# can_12V_step_Ivan.net
KiCad netlist of a schematic drawn in Altium Designer
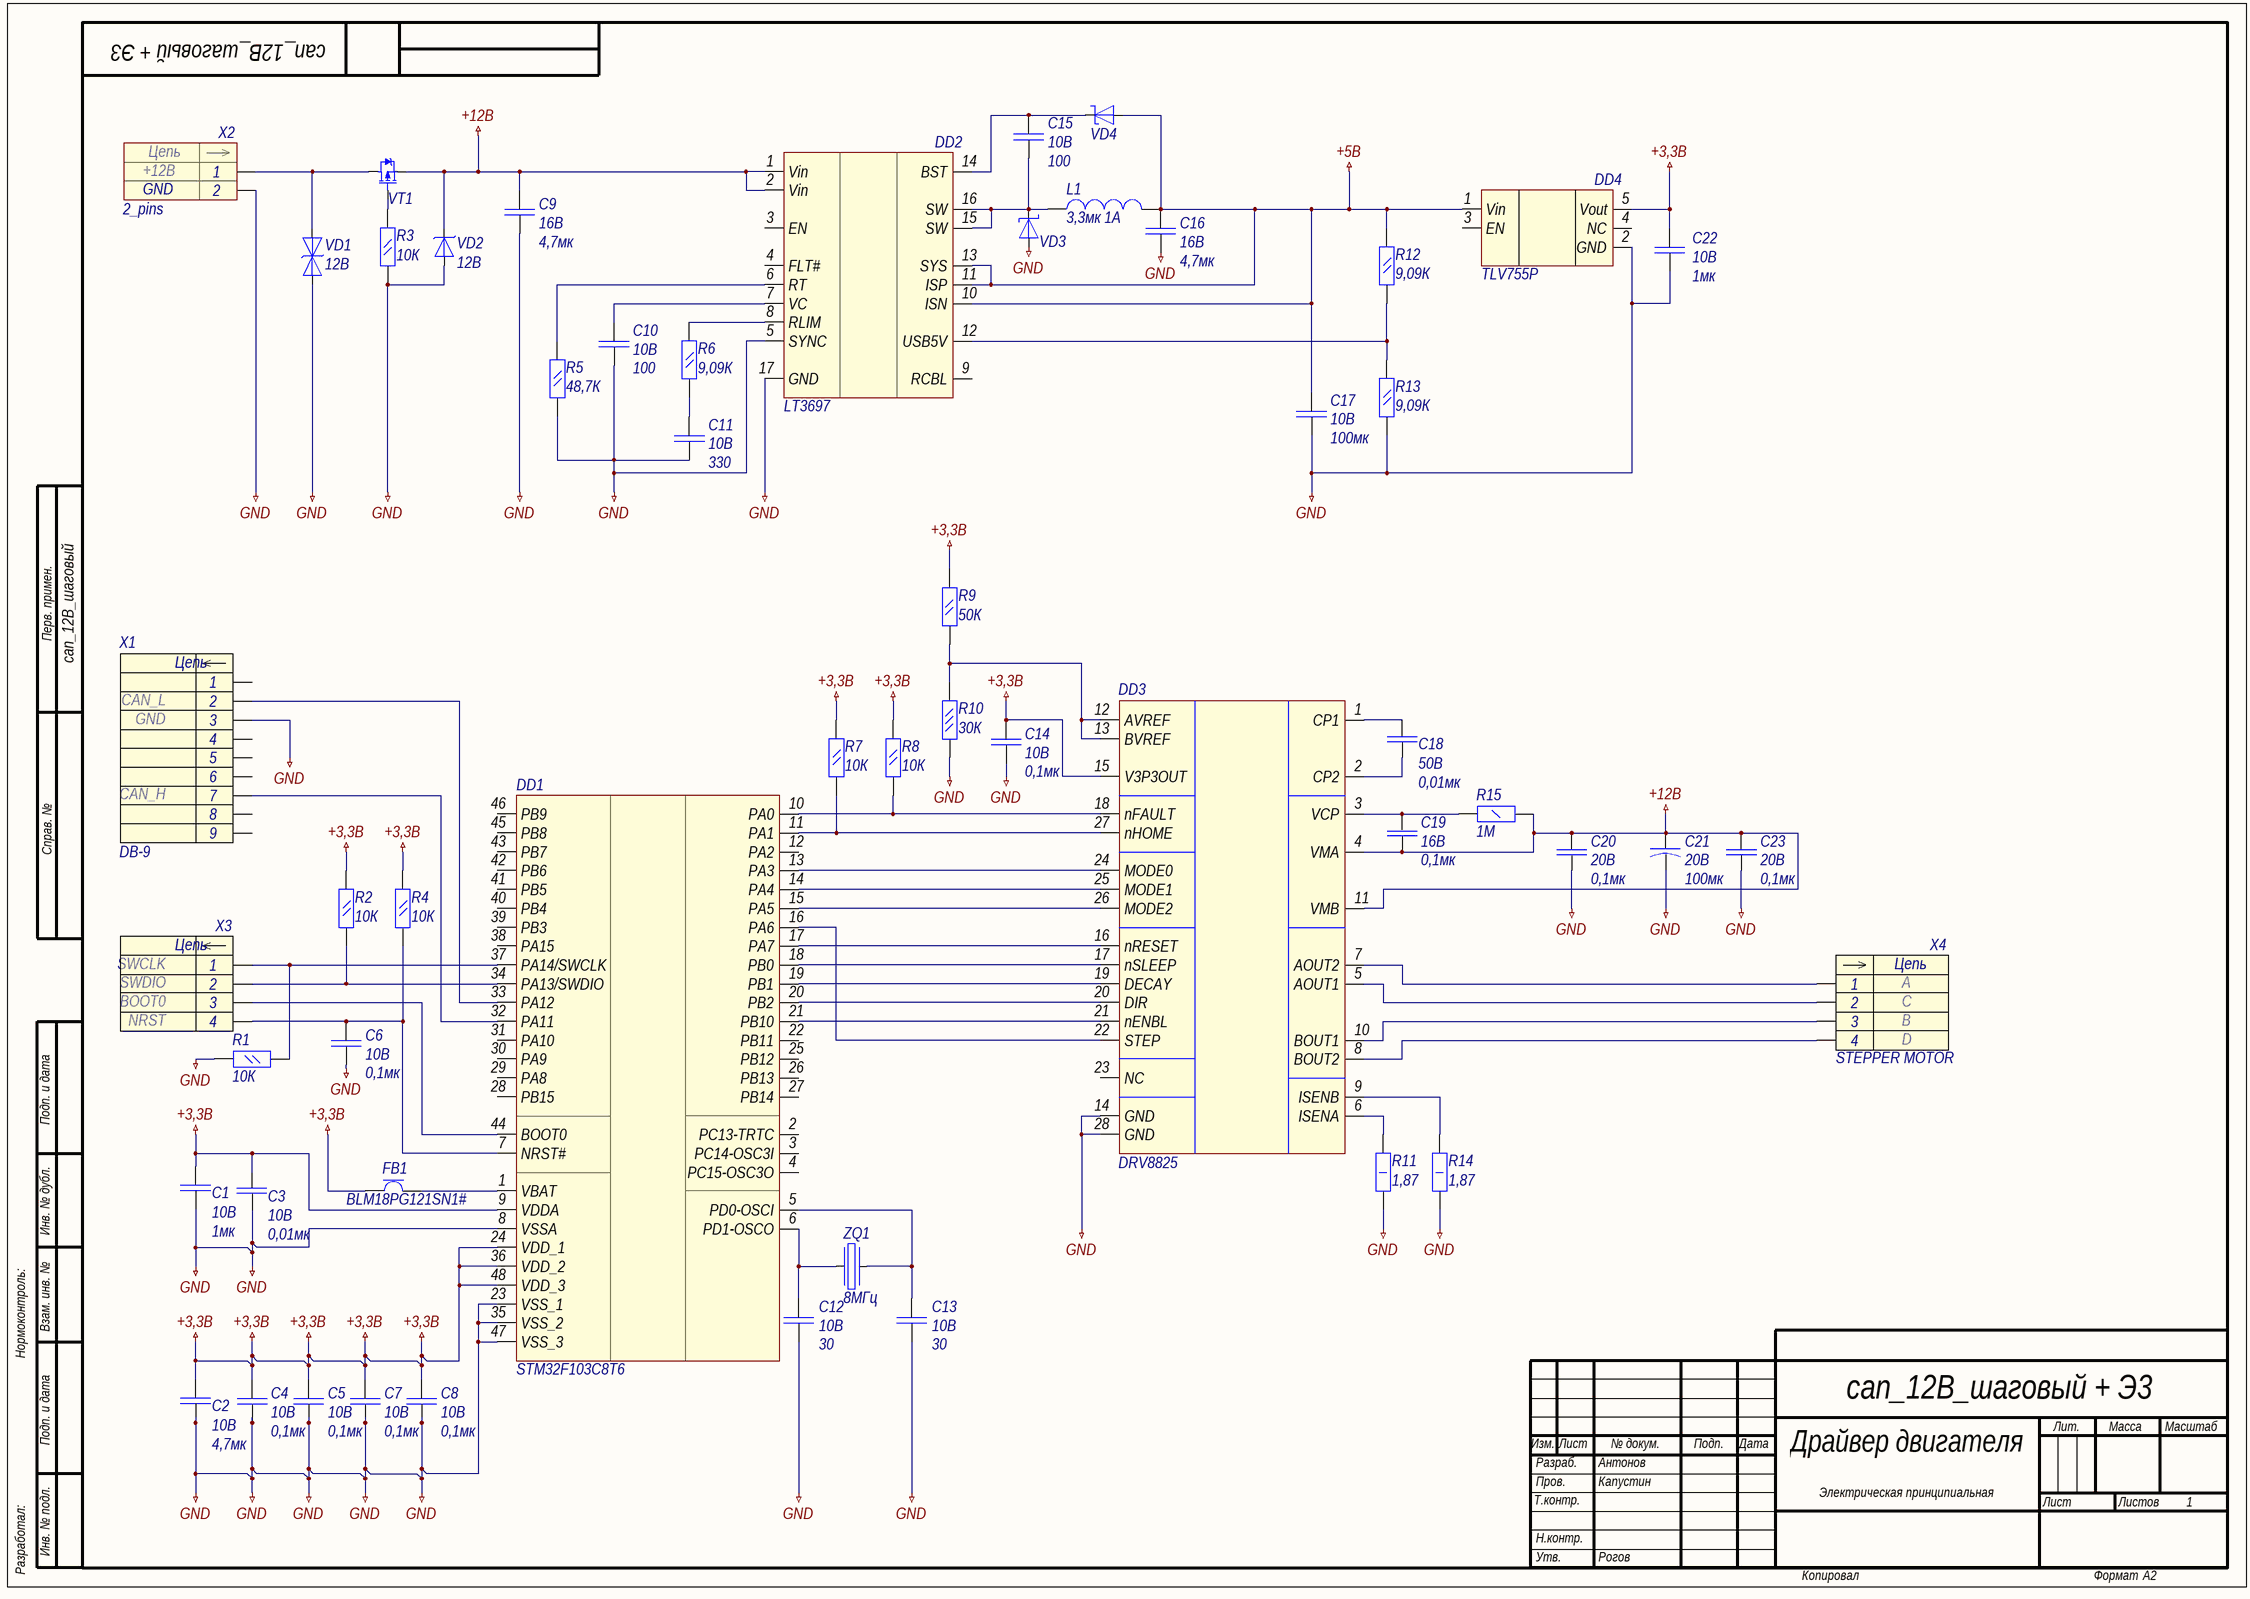
[diagram p0: can_12V_step_Ivan.SchDoc]

(export (version "E")
  (design (tool "Eeschema 10.0.6"))
  (components
    (comp (ref "C1")
      (value "Capacitor")
      (footprint "CH0201C")
      (fields (field (name "VOLTAGE") "10В") (field (name "CAPACITANCE") "1мк"))
      (libsource (lib "") (part "Capacitor_1"))
    )
    (comp (ref "C2")
      (value "Capacitor")
      (footprint "CH0402C")
      (fields (field (name "VOLTAGE") "10В") (field (name "CAPACITANCE") "4,7мк"))
      (libsource (lib "") (part "Capacitor_1"))
    )
    (comp (ref "C3")
      (value "Capacitor")
      (footprint "CH0402C")
      (fields (field (name "VOLTAGE") "10В") (field (name "CAPACITANCE") "0,01мк"))
      (libsource (lib "GOST_Capacitors") (part "Capacitor"))
    )
    (comp (ref "C4")
      (value "Capacitor")
      (footprint "CH0402C")
      (fields (field (name "VOLTAGE") "10В") (field (name "CAPACITANCE") "0,1мк"))
      (libsource (lib "") (part "Capacitor_1"))
    )
    (comp (ref "C5")
      (value "Capacitor")
      (footprint "CH0402C")
      (fields (field (name "VOLTAGE") "10В") (field (name "CAPACITANCE") "0,1мк"))
      (libsource (lib "") (part "Capacitor_1"))
    )
    (comp (ref "C6")
      (value "Capacitor")
      (footprint "CH0402C")
      (fields (field (name "VOLTAGE") "10В") (field (name "CAPACITANCE") "0,1мк"))
      (libsource (lib "") (part "Capacitor_1"))
    )
    (comp (ref "C7")
      (value "Capacitor")
      (footprint "CH0402C")
      (fields (field (name "VOLTAGE") "10В") (field (name "CAPACITANCE") "0,1мк"))
      (libsource (lib "") (part "Capacitor_1"))
    )
    (comp (ref "C8")
      (value "Capacitor")
      (footprint "CH0402C")
      (fields (field (name "VOLTAGE") "10В") (field (name "CAPACITANCE") "0,1мк"))
      (libsource (lib "") (part "Capacitor_1"))
    )
    (comp (ref "C9")
      (value "Capacitor")
      (footprint "CH0603C")
      (fields (field (name "VOLTAGE") "16В") (field (name "CAPACITANCE") "4,7мк"))
      (libsource (lib "") (part "Capacitor_1"))
    )
    (comp (ref "C10")
      (value "Capacitor")
      (footprint "CH0201C")
      (fields (field (name "VOLTAGE") "10В") (field (name "CAPACITANCE") "100"))
      (libsource (lib "") (part "Capacitor_1"))
    )
    (comp (ref "C11")
      (value "Capacitor")
      (footprint "CH0402C")
      (fields (field (name "VOLTAGE") "10В") (field (name "CAPACITANCE") "330"))
      (libsource (lib "") (part "Capacitor_1"))
    )
    (comp (ref "C12")
      (value "Capacitor")
      (footprint "CH0201C")
      (fields (field (name "VOLTAGE") "10В") (field (name "CAPACITANCE") "30"))
      (libsource (lib "") (part "Capacitor_1"))
    )
    (comp (ref "C13")
      (value "Capacitor")
      (footprint "CH0201C")
      (fields (field (name "VOLTAGE") "10В") (field (name "CAPACITANCE") "30"))
      (libsource (lib "") (part "Capacitor_1"))
    )
    (comp (ref "C14")
      (value "Capacitor")
      (footprint "CH0402C")
      (fields (field (name "VOLTAGE") "10В") (field (name "CAPACITANCE") "0,1мк"))
      (libsource (lib "") (part "Capacitor_1"))
    )
    (comp (ref "C15")
      (value "Capacitor")
      (footprint "CH0201C")
      (fields (field (name "VOLTAGE") "10В") (field (name "CAPACITANCE") "100"))
      (libsource (lib "") (part "Capacitor_1"))
    )
    (comp (ref "C16")
      (value "Capacitor")
      (footprint "CH0603C")
      (fields (field (name "VOLTAGE") "16В") (field (name "CAPACITANCE") "4,7мк"))
      (libsource (lib "") (part "Capacitor_1"))
    )
    (comp (ref "C17")
      (value "Capacitor")
      (footprint "CH1206C")
      (fields (field (name "VOLTAGE") "10В") (field (name "CAPACITANCE") "100мк"))
      (libsource (lib "") (part "Capacitor_1"))
    )
    (comp (ref "C18")
      (value "Capacitor")
      (footprint "CH0402C")
      (fields (field (name "VOLTAGE") "50В") (field (name "CAPACITANCE") "0,01мк"))
      (libsource (lib "GOST_Capacitors") (part "Capacitor"))
    )
    (comp (ref "C19")
      (value "Capacitor")
      (footprint "CH0402C")
      (fields (field (name "VOLTAGE") "16В") (field (name "CAPACITANCE") "0,1мк"))
      (libsource (lib "GOST_Capacitors") (part "Capacitor"))
    )
    (comp (ref "C20")
      (value "Capacitor")
      (footprint "CH0805C")
      (fields (field (name "VOLTAGE") "20В") (field (name "CAPACITANCE") "0,1мк"))
      (libsource (lib "GOST_Capacitors") (part "Capacitor"))
    )
    (comp (ref "C21")
      (value "Capacitor_Passing")
      (footprint "RB5-10.5")
      (fields (field (name "VOLTAGE") "20В") (field (name "CAPACITANCE") "100мк"))
      (libsource (lib "GOST_Capacitors") (part "Capacitor_Passing"))
    )
    (comp (ref "C22")
      (value "Capacitor")
      (footprint "CH0201C")
      (fields (field (name "VOLTAGE") "10В") (field (name "CAPACITANCE") "1мк"))
      (libsource (lib "") (part "Capacitor_1"))
    )
    (comp (ref "C23")
      (value "Capacitor")
      (footprint "CH0805C")
      (fields (field (name "VOLTAGE") "20В") (field (name "CAPACITANCE") "0,1мк"))
      (libsource (lib "GOST_Capacitors") (part "Capacitor"))
    )
    (comp (ref "DD1")
      (value "STM32F103C8T6")
      (footprint "STM32F103 48pins")
      (libsource (lib "GOST_lib_devices") (part "STM32"))
    )
    (comp (ref "DD2")
      (value "LT3697")
      (footprint "LT3697")
      (description "6~18 to 5")
      (libsource (lib "GOST_lib_devices") (part "LT3697"))
    )
    (comp (ref "DD3")
      (value "DRV8825")
      (footprint "DRV8825")
      (libsource (lib "GOST_lib_devices") (part "DRV8825"))
    )
    (comp (ref "DD4")
      (value "TLV755P")
      (footprint "SOT23-5")
      (libsource (lib "GOST_lib_devices") (part "LDO +3.3V"))
    )
    (comp (ref "FB1")
      (value "Ferrite bead")
      (footprint "CH0603L")
      (fields (field (name "MODEL") "BLM18PG121SN1#"))
      (libsource (lib "GOST_Inductors") (part "Ferrite bead"))
    )
    (comp (ref "L1")
      (value "*")
      (footprint "CH0805L")
      (fields (field (name "MAX CURRENT") "1А") (field (name "INDUCTANCE") "3,3мк"))
      (libsource (lib "GOST_Inductors") (part "Inductor"))
    )
    (comp (ref "R1")
      (value "Res_0.125")
      (footprint "CH0805R")
      (fields (field (name "IMPEDANCE") "10К"))
      (libsource (lib "GOST_Resistors") (part "Res_0.125"))
    )
    (comp (ref "R2")
      (value "Res_0.125")
      (footprint "CH0805R")
      (fields (field (name "IMPEDANCE") "10К"))
      (libsource (lib "GOST_Resistors") (part "Res_0.125"))
    )
    (comp (ref "R3")
      (value "Res_0.125")
      (footprint "CH0402R")
      (fields (field (name "IMPEDANCE") "10К"))
      (libsource (lib "GOST_Resistors") (part "Res_0.125"))
    )
    (comp (ref "R4")
      (value "Res_0.125")
      (footprint "CH0805R")
      (fields (field (name "IMPEDANCE") "10К"))
      (libsource (lib "GOST_Resistors") (part "Res_0.125"))
    )
    (comp (ref "R5")
      (value "Res_0.125")
      (footprint "CH0805R")
      (fields (field (name "IMPEDANCE") "48,7К"))
      (libsource (lib "GOST_Resistors") (part "Res_0.125"))
    )
    (comp (ref "R6")
      (value "Res_0.125")
      (footprint "CH0805R")
      (fields (field (name "IMPEDANCE") "9,09К"))
      (libsource (lib "GOST_Resistors") (part "Res_0.125"))
    )
    (comp (ref "R7")
      (value "Res_0.125")
      (footprint "CH0805R")
      (fields (field (name "IMPEDANCE") "10К"))
      (libsource (lib "GOST_Resistors") (part "Res_0.125"))
    )
    (comp (ref "R8")
      (value "Res_0.125")
      (footprint "CH0805R")
      (fields (field (name "IMPEDANCE") "10К"))
      (libsource (lib "GOST_Resistors") (part "Res_0.125"))
    )
    (comp (ref "R9")
      (value "Res_0.125")
      (footprint "CH0603R")
      (fields (field (name "POWER") "100мВ") (field (name "IMPEDANCE") "50К"))
      (libsource (lib "") (part "Res_0.125_1"))
    )
    (comp (ref "R10")
      (value "Res_0.05")
      (footprint "CH0201R")
      (fields (field (name "POWER") "0,05В") (field (name "IMPEDANCE") "30К"))
      (libsource (lib "GOST_Resistors") (part "Res_0.05"))
    )
    (comp (ref "R11")
      (value "Res_1")
      (footprint "CH0603R")
      (fields (field (name "POWER") "1Вт") (field (name "IMPEDANCE") "1,87"))
      (libsource (lib "GOST_Resistors") (part "Res_1"))
    )
    (comp (ref "R12")
      (value "Res_0.125")
      (footprint "CH0805R")
      (fields (field (name "IMPEDANCE") "9,09К"))
      (libsource (lib "GOST_Resistors") (part "Res_0.125"))
    )
    (comp (ref "R13")
      (value "Res_0.125")
      (footprint "CH0805R")
      (fields (field (name "IMPEDANCE") "9,09К"))
      (libsource (lib "GOST_Resistors") (part "Res_0.125"))
    )
    (comp (ref "R14")
      (value "Res_1")
      (footprint "CH0603R")
      (fields (field (name "POWER") "1Вт") (field (name "IMPEDANCE") "1,87"))
      (libsource (lib "GOST_Resistors") (part "Res_1"))
    )
    (comp (ref "R15")
      (value "Res_0.5")
      (footprint "CH0805R")
      (fields (field (name "IMPEDANCE") "1М"))
      (libsource (lib "GOST_Resistors") (part "Res_0.5"))
    )
    (comp (ref "VD1")
      (value "TVS-diod_simmetrical")
      (footprint "CH0201L")
      (fields (field (name "MANUFACTURER") "Littelfuse") (field (name "CLAMPING VOLTAGE") "12В"))
      (libsource (lib "GOST_Diodes") (part "TVS-diod_simmetrical"))
    )
    (comp (ref "VD2")
      (value "TVS-diod_directed")
      (footprint "DO214AA")
      (fields (field (name "MANUFACTURER") "Bourns") (field (name "CLAMPING_VOLTAGE") "12В"))
      (libsource (lib "GOST_Diodes") (part "TVS-diod_directed"))
    )
    (comp (ref "VD3")
      (value "Diod Schottky")
      (footprint "DO214AA")
      (fields (field (name "MANUFACTURER") "Rectron"))
      (libsource (lib "GOST_Diodes") (part "Diod Schottky"))
    )
    (comp (ref "VD4")
      (value "Diod Schottky")
      (footprint "SOT23_132")
      (fields (field (name "MANUFACTURER") "Toshiba"))
      (libsource (lib "GOST_Diodes") (part "Diod Schottky"))
    )
    (comp (ref "VT1")
      (value "*")
      (footprint "SOT23_132")
      (libsource (lib "GOST_Transistors") (part "P-Channel"))
    )
    (comp (ref "X1")
      (value "DB-9")
      (footprint "CON: DB-9F")
      (fields (field (name "2") "CAN_L") (field (name "3") "GND") (field (name "7") "CAN_H"))
      (libsource (lib "GOST_lib_connectors") (part "9_pins"))
    )
    (comp (ref "X2")
      (value "2_pins")
      (footprint "CON: 163-179PH-EX")
      (fields (field (name "VCC") "+12В"))
      (libsource (lib "GOST_lib_connectors") (part "2_pins"))
    )
    (comp (ref "X3")
      (value "4_pins")
      (footprint "CON: CWF-4R")
      (fields
        (field (name "2") "SWDIO")
        (field (name "3") "BOOT0")
        (field (name "1") "SWCLK")
        (field (name "4") "NRST")
      )
      (libsource (lib "") (part "4_pins_1"))
    )
    (comp (ref "X4")
      (value "STEPPER MOTOR")
      (footprint "CON: CWF-4R")
      (description "Bipolar Stepper Motor 200 Step 0.35A 12VDC")
      (fields (field (name "2") "C") (field (name "3") "B") (field (name "1") "A") (field (name "4") "D"))
      (libsource (lib "GOST_lib_connectors") (part "4_pins"))
    )
    (comp (ref "ZQ1")
      (value "Oscillator")
      (footprint "OSC: 5032")
      (fields (field (name "FREQ") "8МГц"))
      (libsource (lib "GOST_Miscelanuious") (part "Oscillator"))
    )
  )
  (nets
    (net (code "1") (name "+3,3В") (class "Default")
      (node (ref "C1") (pin "2") (pinfunction "C1-_2") (pintype "power_in"))
      (node (ref "C14") (pin "1") (pinfunction "C1+_1") (pintype "power_in"))
      (node (ref "C2") (pin "2") (pinfunction "C1-_2") (pintype "power_in"))
      (node (ref "C22") (pin "1") (pinfunction "C1+_1") (pintype "power_in"))
      (node (ref "C3") (pin "1") (pinfunction "С+_1") (pintype "power_in"))
      (node (ref "C4") (pin "1") (pinfunction "C1+_1") (pintype "power_in"))
      (node (ref "C5") (pin "1") (pinfunction "C1+_1") (pintype "power_in"))
      (node (ref "C7") (pin "1") (pinfunction "C1+_1") (pintype "power_in"))
      (node (ref "C8") (pin "1") (pinfunction "C1+_1") (pintype "power_in"))
      (node (ref "DD1") (pin "24") (pinfunction "VDD_1_24") (pintype "passive"))
      (node (ref "DD1") (pin "36") (pinfunction "VDD_2_36") (pintype "passive"))
      (node (ref "DD1") (pin "48") (pinfunction "VDD_3_48") (pintype "passive"))
      (node (ref "DD1") (pin "9") (pinfunction "VDDA_9") (pintype "passive"))
      (node (ref "DD3") (pin "15") (pinfunction "V3P3OUT_15") (pintype "power_in"))
      (node (ref "DD4") (pin "5") (pinfunction "Vout_5") (pintype "power_in"))
      (node (ref "FB1") (pin "1") (pintype "power_in"))
      (node (ref "R2") (pin "1") (pinfunction "C1-_1") (pintype "power_in"))
      (node (ref "R4") (pin "1") (pinfunction "C1-_1") (pintype "power_in"))
      (node (ref "R7") (pin "1") (pinfunction "C1-_1") (pintype "power_in"))
      (node (ref "R8") (pin "1") (pinfunction "C1-_1") (pintype "power_in"))
      (node (ref "R9") (pin "2") (pintype "power_in"))
    )
    (net (code "2") (name "+5В") (class "Default")
      (node (ref "C16") (pin "1") (pinfunction "C1+_1") (pintype "power_in"))
      (node (ref "C17") (pin "1") (pinfunction "C1+_1") (pintype "power_in"))
      (node (ref "DD2") (pin "10") (pinfunction "ISN_10") (pintype "power_in"))
      (node (ref "DD2") (pin "11") (pinfunction "ISP_11") (pintype "power_in"))
      (node (ref "DD2") (pin "13") (pinfunction "SYS_13") (pintype "power_in"))
      (node (ref "DD4") (pin "1") (pinfunction "Vin_1") (pintype "power_in"))
      (node (ref "L1") (pin "2") (pinfunction "14_2") (pintype "power_in"))
      (node (ref "R12") (pin "1") (pinfunction "C1-_1") (pintype "power_in"))
      (node (ref "VD4") (pin "1") (pinfunction "1_1") (pintype "passive"))
    )
    (net (code "3") (name "+12В") (class "Default")
      (node (ref "C19") (pin "1") (pinfunction "С+_1") (pintype "power_in"))
      (node (ref "C20") (pin "2") (pinfunction "С-_2") (pintype "power_in"))
      (node (ref "C21") (pin "1") (pinfunction "C+_1") (pintype "power_in"))
      (node (ref "C23") (pin "2") (pinfunction "С-_2") (pintype "power_in"))
      (node (ref "C9") (pin "1") (pinfunction "C1+_1") (pintype "power_in"))
      (node (ref "DD2") (pin "1") (pinfunction "Vin_1") (pintype "power_in"))
      (node (ref "DD2") (pin "2") (pinfunction "Vin_2") (pintype "power_in"))
      (node (ref "DD3") (pin "11") (pinfunction "VMB_11") (pintype "power_in"))
      (node (ref "DD3") (pin "4") (pinfunction "VMA_4") (pintype "power_in"))
      (node (ref "R15") (pin "1") (pinfunction "C1-_1") (pintype "power_in"))
      (node (ref "VD2") (pin "2") (pinfunction "C_2") (pintype "passive"))
      (node (ref "VT1") (pin "3") (pinfunction "S_3") (pintype "passive"))
    )
    (net (code "4") (name "GND") (class "Default")
      (node (ref "C1") (pin "1") (pinfunction "C1+_1") (pintype "power_in"))
      (node (ref "C10") (pin "2") (pinfunction "C1-_2") (pintype "power_in"))
      (node (ref "C11") (pin "2") (pinfunction "C1-_2") (pintype "power_in"))
      (node (ref "C12") (pin "2") (pinfunction "C1-_2") (pintype "power_in"))
      (node (ref "C13") (pin "2") (pinfunction "C1-_2") (pintype "power_in"))
      (node (ref "C14") (pin "2") (pinfunction "C1-_2") (pintype "power_in"))
      (node (ref "C16") (pin "2") (pinfunction "C1-_2") (pintype "power_in"))
      (node (ref "C17") (pin "2") (pinfunction "C1-_2") (pintype "power_in"))
      (node (ref "C2") (pin "1") (pinfunction "C1+_1") (pintype "power_in"))
      (node (ref "C20") (pin "1") (pinfunction "С+_1") (pintype "power_in"))
      (node (ref "C21") (pin "2") (pinfunction "C-_2") (pintype "power_in"))
      (node (ref "C22") (pin "2") (pinfunction "C1-_2") (pintype "power_in"))
      (node (ref "C23") (pin "1") (pinfunction "С+_1") (pintype "power_in"))
      (node (ref "C3") (pin "2") (pinfunction "С-_2") (pintype "power_in"))
      (node (ref "C4") (pin "2") (pinfunction "C1-_2") (pintype "power_in"))
      (node (ref "C5") (pin "2") (pinfunction "C1-_2") (pintype "power_in"))
      (node (ref "C6") (pin "2") (pinfunction "C1-_2") (pintype "power_in"))
      (node (ref "C7") (pin "2") (pinfunction "C1-_2") (pintype "power_in"))
      (node (ref "C8") (pin "2") (pinfunction "C1-_2") (pintype "power_in"))
      (node (ref "C9") (pin "2") (pinfunction "C1-_2") (pintype "power_in"))
      (node (ref "DD1") (pin "23") (pinfunction "VSS_1_23") (pintype "passive"))
      (node (ref "DD1") (pin "35") (pinfunction "VSS_2_35") (pintype "passive"))
      (node (ref "DD1") (pin "47") (pinfunction "VSS_3_47") (pintype "passive"))
      (node (ref "DD1") (pin "8") (pinfunction "VSSA_8") (pintype "passive"))
      (node (ref "DD2") (pin "17") (pinfunction "GND_17") (pintype "power_in"))
      (node (ref "DD2") (pin "5") (pinfunction "SYNC_5") (pintype "power_in"))
      (node (ref "DD3") (pin "14") (pinfunction "GND_14") (pintype "power_in"))
      (node (ref "DD3") (pin "28") (pinfunction "GND_28") (pintype "power_in"))
      (node (ref "DD4") (pin "2") (pinfunction "GND_2") (pintype "power_in"))
      (node (ref "R1") (pin "1") (pinfunction "C1-_1") (pintype "power_in"))
      (node (ref "R10") (pin "1") (pintype "power_in"))
      (node (ref "R11") (pin "1") (pinfunction "*_1") (pintype "power_in"))
      (node (ref "R13") (pin "2") (pinfunction "C1-_2") (pintype "power_in"))
      (node (ref "R14") (pin "1") (pinfunction "*_1") (pintype "power_in"))
      (node (ref "R3") (pin "1") (pinfunction "C1-_1") (pintype "power_in"))
      (node (ref "R5") (pin "2") (pinfunction "C1-_2") (pintype "power_in"))
      (node (ref "VD1") (pin "1") (pinfunction "A_1") (pintype "passive"))
      (node (ref "VD2") (pin "1") (pinfunction "A_1") (pintype "passive"))
      (node (ref "VD3") (pin "1") (pinfunction "1_1") (pintype "passive"))
      (node (ref "X1") (pin "3") (pinfunction "3_3") (pintype "passive"))
      (node (ref "X2") (pin "2") (pinfunction "2_2") (pintype "passive"))
    )
    (net (code "5") (name "Net-(C6-C1+)") (class "Default")
      (node (ref "C6") (pin "1") (pinfunction "C1+_1") (pintype "power_in"))
      (node (ref "DD1") (pin "7") (pinfunction "NRST#_7") (pintype "passive"))
      (node (ref "R4") (pin "2") (pinfunction "C1-_2") (pintype "power_in"))
      (node (ref "X3") (pin "4") (pinfunction "4_4") (pintype "passive"))
    )
    (net (code "6") (name "Net-(C10-C1+)") (class "Default")
      (node (ref "C10") (pin "1") (pinfunction "C1+_1") (pintype "power_in"))
      (node (ref "DD2") (pin "7") (pinfunction "VC_7") (pintype "power_in"))
    )
    (net (code "7") (name "Net-(C11-C1+)") (class "Default")
      (node (ref "C11") (pin "1") (pinfunction "C1+_1") (pintype "power_in"))
      (node (ref "R6") (pin "2") (pinfunction "C1-_2") (pintype "power_in"))
    )
    (net (code "8") (name "Net-(C12-C1+)") (class "Default")
      (node (ref "C12") (pin "1") (pinfunction "C1+_1") (pintype "power_in"))
      (node (ref "DD1") (pin "6") (pinfunction "PD1-OSCO_6") (pintype "passive"))
      (node (ref "ZQ1") (pin "1") (pintype "passive"))
    )
    (net (code "9") (name "Net-(C13-C1+)") (class "Default")
      (node (ref "C13") (pin "1") (pinfunction "C1+_1") (pintype "power_in"))
      (node (ref "DD1") (pin "5") (pinfunction "PD0-OSCI_5") (pintype "passive"))
      (node (ref "ZQ1") (pin "3") (pintype "passive"))
    )
    (net (code "10") (name "Net-(C15-C1+)") (class "Default")
      (node (ref "C15") (pin "1") (pinfunction "C1+_1") (pintype "power_in"))
      (node (ref "DD2") (pin "14") (pinfunction "BST_14") (pintype "power_in"))
      (node (ref "VD4") (pin "2") (pinfunction "2_2") (pintype "passive"))
    )
    (net (code "11") (name "Net-(C15-C1-)") (class "Default")
      (node (ref "C15") (pin "2") (pinfunction "C1-_2") (pintype "power_in"))
      (node (ref "DD2") (pin "15") (pinfunction "SW_15") (pintype "power_in"))
      (node (ref "DD2") (pin "16") (pinfunction "SW_16") (pintype "power_in"))
      (node (ref "L1") (pin "1") (pinfunction "C1-_1") (pintype "power_in"))
      (node (ref "VD3") (pin "2") (pinfunction "2_2") (pintype "passive"))
    )
    (net (code "12") (name "Net-(C18-С+)") (class "Default")
      (node (ref "C18") (pin "1") (pinfunction "С+_1") (pintype "power_in"))
      (node (ref "DD3") (pin "2") (pinfunction "CP2_2") (pintype "power_in"))
    )
    (net (code "13") (name "Net-(C18-С-)") (class "Default")
      (node (ref "C18") (pin "2") (pinfunction "С-_2") (pintype "power_in"))
      (node (ref "DD3") (pin "1") (pinfunction "CP1_1") (pintype "power_in"))
    )
    (net (code "14") (name "Net-(C19-С-)") (class "Default")
      (node (ref "C19") (pin "2") (pinfunction "С-_2") (pintype "power_in"))
      (node (ref "DD3") (pin "3") (pinfunction "VCP_3") (pintype "power_in"))
      (node (ref "R15") (pin "2") (pinfunction "C1-_2") (pintype "power_in"))
    )
    (net (code "15") (name "Net-(DD1-BOOT0)") (class "Default")
      (node (ref "DD1") (pin "44") (pinfunction "BOOT0_44") (pintype "passive"))
      (node (ref "X3") (pin "3") (pinfunction "3_3") (pintype "passive"))
    )
    (net (code "16") (name "Net-(DD1-PA0)") (class "Default")
      (node (ref "DD1") (pin "10") (pinfunction "PA0_10") (pintype "passive"))
      (node (ref "DD3") (pin "18") (pinfunction "nFAULT_18") (pintype "power_in"))
      (node (ref "R8") (pin "2") (pinfunction "C1-_2") (pintype "power_in"))
    )
    (net (code "17") (name "Net-(DD1-PA1)") (class "Default")
      (node (ref "DD1") (pin "11") (pinfunction "PA1_11") (pintype "passive"))
      (node (ref "DD3") (pin "27") (pinfunction "nHOME_27") (pintype "power_in"))
      (node (ref "R7") (pin "2") (pinfunction "C1-_2") (pintype "power_in"))
    )
    (net (code "18") (name "Net-(DD1-PA3)") (class "Default")
      (node (ref "DD1") (pin "13") (pinfunction "PA3_13") (pintype "passive"))
      (node (ref "DD3") (pin "24") (pinfunction "MODE0_24") (pintype "power_in"))
    )
    (net (code "19") (name "Net-(DD1-PA4)") (class "Default")
      (node (ref "DD1") (pin "14") (pinfunction "PA4_14") (pintype "passive"))
      (node (ref "DD3") (pin "25") (pinfunction "MODE1_25") (pintype "power_in"))
    )
    (net (code "20") (name "Net-(DD1-PA5)") (class "Default")
      (node (ref "DD1") (pin "15") (pinfunction "PA5_15") (pintype "passive"))
      (node (ref "DD3") (pin "26") (pinfunction "MODE2_26") (pintype "power_in"))
    )
    (net (code "21") (name "Net-(DD1-PA6)") (class "Default")
      (node (ref "DD1") (pin "16") (pinfunction "PA6_16") (pintype "passive"))
      (node (ref "DD3") (pin "22") (pinfunction "STEP_22") (pintype "power_in"))
    )
    (net (code "22") (name "Net-(DD1-PA7)") (class "Default")
      (node (ref "DD1") (pin "17") (pinfunction "PA7_17") (pintype "passive"))
      (node (ref "DD3") (pin "16") (pinfunction "nRESET_16") (pintype "power_in"))
    )
    (net (code "23") (name "Net-(DD1-PA11)") (class "Default")
      (node (ref "DD1") (pin "32") (pinfunction "PA11_32") (pintype "passive"))
      (node (ref "X1") (pin "7") (pinfunction "7_7") (pintype "power_in"))
    )
    (net (code "24") (name "Net-(DD1-PA12)") (class "Default")
      (node (ref "DD1") (pin "33") (pinfunction "PA12_33") (pintype "passive"))
      (node (ref "X1") (pin "2") (pinfunction "2_2") (pintype "passive"))
    )
    (net (code "25") (name "Net-(DD1-PA13{slash}SWDIO)") (class "Default")
      (node (ref "DD1") (pin "34") (pinfunction "PA13/SWDIO_34") (pintype "passive"))
      (node (ref "R2") (pin "2") (pinfunction "C1-_2") (pintype "power_in"))
      (node (ref "X3") (pin "2") (pinfunction "2_2") (pintype "passive"))
    )
    (net (code "26") (name "Net-(DD1-PA14{slash}SWCLK)") (class "Default")
      (node (ref "DD1") (pin "37") (pinfunction "PA14/SWCLK_37") (pintype "passive"))
      (node (ref "R1") (pin "2") (pinfunction "C1-_2") (pintype "power_in"))
      (node (ref "X3") (pin "1") (pinfunction "1_1") (pintype "passive"))
    )
    (net (code "27") (name "Net-(DD1-PB0)") (class "Default")
      (node (ref "DD1") (pin "18") (pinfunction "PB0_18") (pintype "passive"))
      (node (ref "DD3") (pin "17") (pinfunction "nSLEEP_17") (pintype "power_in"))
    )
    (net (code "28") (name "Net-(DD1-PB1)") (class "Default")
      (node (ref "DD1") (pin "19") (pinfunction "PB1_19") (pintype "passive"))
      (node (ref "DD3") (pin "19") (pinfunction "DECAY_19") (pintype "power_in"))
    )
    (net (code "29") (name "Net-(DD1-PB2)") (class "Default")
      (node (ref "DD1") (pin "20") (pinfunction "PB2_20") (pintype "passive"))
      (node (ref "DD3") (pin "20") (pinfunction "DIR_20") (pintype "power_in"))
    )
    (net (code "30") (name "Net-(DD1-PB10)") (class "Default")
      (node (ref "DD1") (pin "21") (pinfunction "PB10_21") (pintype "passive"))
      (node (ref "DD3") (pin "21") (pinfunction "nENBL_21") (pintype "power_in"))
    )
    (net (code "31") (name "Net-(DD1-VBAT)") (class "Default")
      (node (ref "DD1") (pin "1") (pinfunction "VBAT_1") (pintype "passive"))
      (node (ref "FB1") (pin "2") (pintype "power_in"))
    )
    (net (code "32") (name "Net-(DD2-RLIM)") (class "Default")
      (node (ref "DD2") (pin "8") (pinfunction "RLIM_8") (pintype "power_in"))
      (node (ref "R6") (pin "1") (pinfunction "C1-_1") (pintype "power_in"))
    )
    (net (code "33") (name "Net-(DD2-RT)") (class "Default")
      (node (ref "DD2") (pin "6") (pinfunction "RT_6") (pintype "power_in"))
      (node (ref "R5") (pin "1") (pinfunction "C1-_1") (pintype "power_in"))
    )
    (net (code "34") (name "Net-(DD2-USB5V)") (class "Default")
      (node (ref "DD2") (pin "12") (pinfunction "USB5V_12") (pintype "power_in"))
      (node (ref "R12") (pin "2") (pinfunction "C1-_2") (pintype "power_in"))
      (node (ref "R13") (pin "1") (pinfunction "C1-_1") (pintype "power_in"))
    )
    (net (code "35") (name "Net-(DD3-AOUT1)") (class "Default")
      (node (ref "DD3") (pin "5") (pinfunction "AOUT1_5") (pintype "power_in"))
      (node (ref "X4") (pin "2") (pinfunction "2_2") (pintype "passive"))
    )
    (net (code "36") (name "Net-(DD3-AOUT2)") (class "Default")
      (node (ref "DD3") (pin "7") (pinfunction "AOUT2_7") (pintype "power_in"))
      (node (ref "X4") (pin "1") (pinfunction "1_1") (pintype "passive"))
    )
    (net (code "37") (name "Net-(DD3-AVREF)") (class "Default")
      (node (ref "DD3") (pin "12") (pinfunction "AVREF_12") (pintype "power_in"))
      (node (ref "DD3") (pin "13") (pinfunction "BVREF_13") (pintype "power_in"))
      (node (ref "R10") (pin "2") (pintype "power_in"))
      (node (ref "R9") (pin "1") (pintype "power_in"))
    )
    (net (code "38") (name "Net-(DD3-BOUT1)") (class "Default")
      (node (ref "DD3") (pin "10") (pinfunction "BOUT1_10") (pintype "power_in"))
      (node (ref "X4") (pin "3") (pinfunction "3_3") (pintype "passive"))
    )
    (net (code "39") (name "Net-(DD3-BOUT2)") (class "Default")
      (node (ref "DD3") (pin "8") (pinfunction "BOUT2_8") (pintype "power_in"))
      (node (ref "X4") (pin "4") (pinfunction "4_4") (pintype "passive"))
    )
    (net (code "40") (name "Net-(DD3-ISENA)") (class "Default")
      (node (ref "DD3") (pin "6") (pinfunction "ISENA_6") (pintype "power_in"))
      (node (ref "R11") (pin "2") (pinfunction "*_2") (pintype "power_in"))
    )
    (net (code "41") (name "Net-(DD3-ISENB)") (class "Default")
      (node (ref "DD3") (pin "9") (pinfunction "ISENB_9") (pintype "power_in"))
      (node (ref "R14") (pin "2") (pinfunction "*_2") (pintype "power_in"))
    )
    (net (code "42") (name "Net-(VD1-C)") (class "Default")
      (node (ref "VD1") (pin "2") (pinfunction "C_2") (pintype "passive"))
      (node (ref "VT1") (pin "2") (pinfunction "D_2") (pintype "passive"))
      (node (ref "X2") (pin "1") (pinfunction "1_1") (pintype "passive"))
    )
    (net (code "43") (name "Net-(VT1-G)") (class "Default")
      (node (ref "R3") (pin "2") (pinfunction "C1-_2") (pintype "power_in"))
      (node (ref "VT1") (pin "1") (pinfunction "G_1") (pintype "passive"))
    )
    (net (code "44") (name "unconnected-(DD1-PA2-Pad12)") (class "Default")
      (node (ref "DD1") (pin "12") (pinfunction "PA2_12") (pintype "passive"))
    )
    (net (code "45") (name "unconnected-(DD1-PA8-Pad29)") (class "Default")
      (node (ref "DD1") (pin "29") (pinfunction "PA8_29") (pintype "passive"))
    )
    (net (code "46") (name "unconnected-(DD1-PA9-Pad30)") (class "Default")
      (node (ref "DD1") (pin "30") (pinfunction "PA9_30") (pintype "passive"))
    )
    (net (code "47") (name "unconnected-(DD1-PA10-Pad31)") (class "Default")
      (node (ref "DD1") (pin "31") (pinfunction "PA10_31") (pintype "passive"))
    )
    (net (code "48") (name "unconnected-(DD1-PA15-Pad38)") (class "Default")
      (node (ref "DD1") (pin "38") (pinfunction "PA15_38") (pintype "passive"))
    )
    (net (code "49") (name "unconnected-(DD1-PB3-Pad39)") (class "Default")
      (node (ref "DD1") (pin "39") (pinfunction "PB3_39") (pintype "passive"))
    )
    (net (code "50") (name "unconnected-(DD1-PB4-Pad40)") (class "Default")
      (node (ref "DD1") (pin "40") (pinfunction "PB4_40") (pintype "passive"))
    )
    (net (code "51") (name "unconnected-(DD1-PB5-Pad41)") (class "Default")
      (node (ref "DD1") (pin "41") (pinfunction "PB5_41") (pintype "passive"))
    )
    (net (code "52") (name "unconnected-(DD1-PB6-Pad42)") (class "Default")
      (node (ref "DD1") (pin "42") (pinfunction "PB6_42") (pintype "passive"))
    )
    (net (code "53") (name "unconnected-(DD1-PB7-Pad43)") (class "Default")
      (node (ref "DD1") (pin "43") (pinfunction "PB7_43") (pintype "passive"))
    )
    (net (code "54") (name "unconnected-(DD1-PB8-Pad45)") (class "Default")
      (node (ref "DD1") (pin "45") (pinfunction "PB8_45") (pintype "passive"))
    )
    (net (code "55") (name "unconnected-(DD1-PB9-Pad46)") (class "Default")
      (node (ref "DD1") (pin "46") (pinfunction "PB9_46") (pintype "passive"))
    )
    (net (code "56") (name "unconnected-(DD1-PB11-Pad22)") (class "Default")
      (node (ref "DD1") (pin "22") (pinfunction "PB11_22") (pintype "passive"))
    )
    (net (code "57") (name "unconnected-(DD1-PB12-Pad25)") (class "Default")
      (node (ref "DD1") (pin "25") (pinfunction "PB12_25") (pintype "passive"))
    )
    (net (code "58") (name "unconnected-(DD1-PB13-Pad26)") (class "Default")
      (node (ref "DD1") (pin "26") (pinfunction "PB13_26") (pintype "passive"))
    )
    (net (code "59") (name "unconnected-(DD1-PB14-Pad27)") (class "Default")
      (node (ref "DD1") (pin "27") (pinfunction "PB14_27") (pintype "passive"))
    )
    (net (code "60") (name "unconnected-(DD1-PB15-Pad28)") (class "Default")
      (node (ref "DD1") (pin "28") (pinfunction "PB15_28") (pintype "passive"))
    )
    (net (code "61") (name "unconnected-(DD1-PC13-TRTC-Pad2)") (class "Default")
      (node (ref "DD1") (pin "2") (pinfunction "PC13-TRTC_2") (pintype "passive"))
    )
    (net (code "62") (name "unconnected-(DD1-PC14-OSC3I-Pad3)") (class "Default")
      (node (ref "DD1") (pin "3") (pinfunction "PC14-OSC3I_3") (pintype "passive"))
    )
    (net (code "63") (name "unconnected-(DD1-PC15-OSC3O-Pad4)") (class "Default")
      (node (ref "DD1") (pin "4") (pinfunction "PC15-OSC3O_4") (pintype "passive"))
    )
    (net (code "64") (name "unconnected-(DD2-EN-Pad3)") (class "Default")
      (node (ref "DD2") (pin "3") (pinfunction "EN_3") (pintype "power_in"))
    )
    (net (code "65") (name "unconnected-(DD2-FLT#-Pad4)") (class "Default")
      (node (ref "DD2") (pin "4") (pinfunction "FLT#_4") (pintype "power_in"))
    )
    (net (code "66") (name "unconnected-(DD2-RCBL-Pad9)") (class "Default")
      (node (ref "DD2") (pin "9") (pinfunction "RCBL_9") (pintype "power_in"))
    )
    (net (code "67") (name "unconnected-(DD3-NC-Pad23)") (class "Default")
      (node (ref "DD3") (pin "23") (pinfunction "NC_23") (pintype "power_in"))
    )
    (net (code "68") (name "unconnected-(DD4-EN-Pad3)") (class "Default")
      (node (ref "DD4") (pin "3") (pinfunction "EN_3") (pintype "power_in"))
    )
    (net (code "69") (name "unconnected-(DD4-NC-Pad4)") (class "Default")
      (node (ref "DD4") (pin "4") (pinfunction "NC_4") (pintype "power_in"))
    )
    (net (code "70") (name "unconnected-(X1-Pad1)") (class "Default")
      (node (ref "X1") (pin "1") (pinfunction "1_1") (pintype "passive"))
    )
    (net (code "71") (name "unconnected-(X1-Pad4)") (class "Default")
      (node (ref "X1") (pin "4") (pinfunction "4_4") (pintype "passive"))
    )
    (net (code "72") (name "unconnected-(X1-Pad5)") (class "Default")
      (node (ref "X1") (pin "5") (pinfunction "5_5") (pintype "passive"))
    )
    (net (code "73") (name "unconnected-(X1-Pad6)") (class "Default")
      (node (ref "X1") (pin "6") (pinfunction "6_6") (pintype "passive"))
    )
    (net (code "74") (name "unconnected-(X1-Pad8)") (class "Default")
      (node (ref "X1") (pin "8") (pinfunction "8_8") (pintype "power_in"))
    )
    (net (code "75") (name "unconnected-(X1-Pad9)") (class "Default")
      (node (ref "X1") (pin "9") (pinfunction "9_9") (pintype "power_in"))
    )
  )
)
